# Bus_Isolator.net
KiCad netlist of a schematic drawn in EAGLE
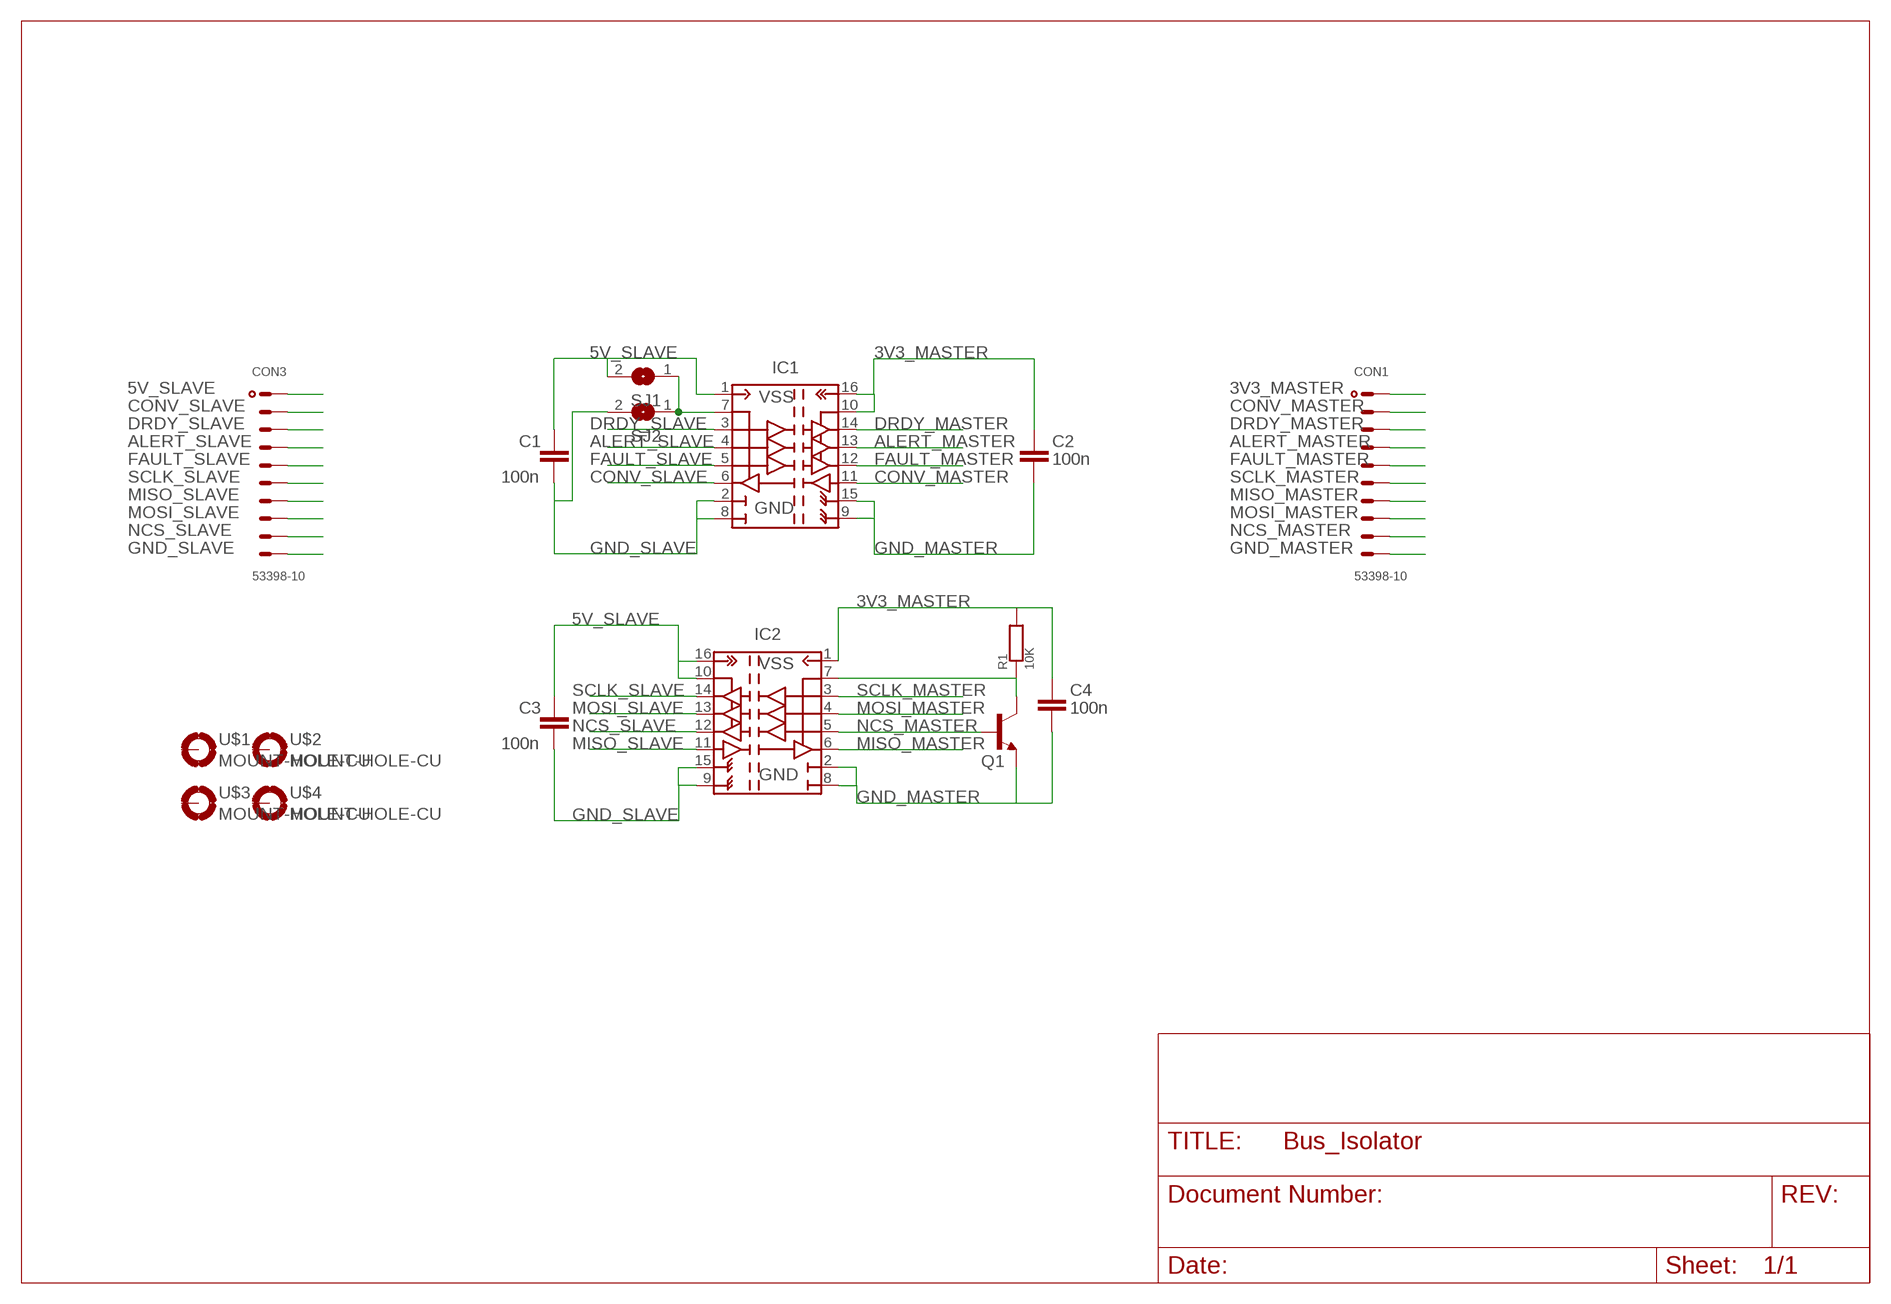
[diagram p0: schematic, sheet 1]

(export (version "E")
  (design (tool "Eeschema 10.0.6"))
  (components
    (comp (ref "C1")
      (value "100n")
      (footprint "eagle-import:C0805")
      (libsource (lib "eagle-import") (part "CSTD"))
    )
    (comp (ref "C2")
      (value "100n")
      (footprint "eagle-import:C0805")
      (libsource (lib "eagle-import") (part "CSTD"))
    )
    (comp (ref "C3")
      (value "100n")
      (footprint "eagle-import:C0805")
      (libsource (lib "eagle-import") (part "CSTD"))
    )
    (comp (ref "C4")
      (value "100n")
      (footprint "eagle-import:C0805")
      (libsource (lib "eagle-import") (part "CSTD"))
    )
    (comp (ref "CON1")
      (value "53398-10")
      (footprint "eagle-import:53398-10")
      (libsource (lib "eagle-import") (part "53?-10398"))
    )
    (comp (ref "CON3")
      (value "53398-10")
      (footprint "eagle-import:53398-10")
      (libsource (lib "eagle-import") (part "53?-10398"))
    )
    (comp (ref "IC1")
      (value "ISO7241")
      (footprint "eagle-import:R-PDSO-G16")
      (libsource (lib "eagle-import") (part "ISO7241"))
    )
    (comp (ref "IC2")
      (value "ISO7241")
      (footprint "eagle-import:R-PDSO-G16")
      (libsource (lib "eagle-import") (part "ISO7241"))
    )
    (comp (ref "Q1")
      (value "TRANSISTOR_NPNSOT23")
      (footprint "eagle-import:SOT23")
      (libsource (lib "eagle-import") (part "TRANSISTOR_NPNSOT23"))
    )
    (comp (ref "R1")
      (value "10K")
      (footprint "eagle-import:R0805")
      (libsource (lib "eagle-import") (part "R"))
    )
    (comp (ref "SJ1") (value "SJ") (footprint "eagle-import:SJ") (libsource (lib "eagle-import") (part "SJ")))
    (comp (ref "SJ2") (value "SJ") (footprint "eagle-import:SJ") (libsource (lib "eagle-import") (part "SJ")))
    (comp (ref "U$1")
      (value "MOUNT-HOLE-CU")
      (footprint "eagle-import:BOHRUNG-3,2-NUR-KUPFER")
      (libsource (lib "eagle-import") (part "MOUNT-HOLE-CU"))
    )
    (comp (ref "U$2")
      (value "MOUNT-HOLE-CU")
      (footprint "eagle-import:BOHRUNG-3,2-NUR-KUPFER")
      (libsource (lib "eagle-import") (part "MOUNT-HOLE-CU"))
    )
    (comp (ref "U$3")
      (value "MOUNT-HOLE-CU")
      (footprint "eagle-import:BOHRUNG-3,2-NUR-KUPFER")
      (libsource (lib "eagle-import") (part "MOUNT-HOLE-CU"))
    )
    (comp (ref "U$4")
      (value "MOUNT-HOLE-CU")
      (footprint "eagle-import:BOHRUNG-3,2-NUR-KUPFER")
      (libsource (lib "eagle-import") (part "MOUNT-HOLE-CU"))
    )
  )
  (nets
    (net (code "1") (name "/3V3_MASTER") (class "Default")
      (node (ref "C2") (pin "2") (pinfunction "2_2") (pintype "passive"))
      (node (ref "C4") (pin "2") (pinfunction "2_2") (pintype "passive"))
      (node (ref "CON1") (pin "1") (pinfunction "1_1") (pintype "passive"))
      (node (ref "IC1") (pin "10") (pinfunction "EN2_10") (pintype "bidirectional"))
      (node (ref "IC1") (pin "16") (pinfunction "VCC2_16") (pintype "bidirectional"))
      (node (ref "IC2") (pin "1") (pinfunction "VCC1_1") (pintype "bidirectional"))
      (node (ref "R1") (pin "2") (pinfunction "2_2") (pintype "passive"))
    )
    (net (code "2") (name "/5V_SLAVE") (class "Default")
      (node (ref "C1") (pin "2") (pinfunction "2_2") (pintype "passive"))
      (node (ref "C3") (pin "2") (pinfunction "2_2") (pintype "passive"))
      (node (ref "CON3") (pin "1") (pinfunction "1_1") (pintype "passive"))
      (node (ref "IC1") (pin "1") (pinfunction "VCC1_1") (pintype "bidirectional"))
      (node (ref "IC2") (pin "10") (pinfunction "EN2_10") (pintype "bidirectional"))
      (node (ref "IC2") (pin "16") (pinfunction "VCC2_16") (pintype "bidirectional"))
      (node (ref "SJ1") (pin "2") (pinfunction "2_2") (pintype "passive"))
    )
    (net (code "3") (name "/ALERT_MASTER") (class "Default")
      (node (ref "CON1") (pin "4") (pinfunction "4_4") (pintype "passive"))
      (node (ref "IC1") (pin "13") (pinfunction "OUT_B_13") (pintype "bidirectional"))
    )
    (net (code "4") (name "/ALERT_SLAVE") (class "Default")
      (node (ref "CON3") (pin "4") (pinfunction "4_4") (pintype "passive"))
      (node (ref "IC1") (pin "4") (pinfunction "IN_B_4") (pintype "bidirectional"))
    )
    (net (code "5") (name "/CONV_MASTER") (class "Default")
      (node (ref "CON1") (pin "2") (pinfunction "2_2") (pintype "passive"))
      (node (ref "IC1") (pin "11") (pinfunction "IN_D_11") (pintype "bidirectional"))
    )
    (net (code "6") (name "/CONV_SLAVE") (class "Default")
      (node (ref "CON3") (pin "2") (pinfunction "2_2") (pintype "passive"))
      (node (ref "IC1") (pin "6") (pinfunction "OUT_D_6") (pintype "bidirectional"))
    )
    (net (code "7") (name "/DRDY_MASTER") (class "Default")
      (node (ref "CON1") (pin "3") (pinfunction "3_3") (pintype "passive"))
      (node (ref "IC1") (pin "14") (pinfunction "OUT_A_14") (pintype "bidirectional"))
    )
    (net (code "8") (name "/DRDY_SLAVE") (class "Default")
      (node (ref "CON3") (pin "3") (pinfunction "3_3") (pintype "passive"))
      (node (ref "IC1") (pin "3") (pinfunction "IN_A_3") (pintype "bidirectional"))
    )
    (net (code "9") (name "/FAULT_MASTER") (class "Default")
      (node (ref "CON1") (pin "5") (pinfunction "5_5") (pintype "passive"))
      (node (ref "IC1") (pin "12") (pinfunction "OUT_C_12") (pintype "bidirectional"))
    )
    (net (code "10") (name "/FAULT_SLAVE") (class "Default")
      (node (ref "CON3") (pin "5") (pinfunction "5_5") (pintype "passive"))
      (node (ref "IC1") (pin "5") (pinfunction "IN_C_5") (pintype "bidirectional"))
    )
    (net (code "11") (name "/GND_MASTER") (class "Default")
      (node (ref "C2") (pin "1") (pinfunction "1_1") (pintype "passive"))
      (node (ref "C4") (pin "1") (pinfunction "1_1") (pintype "passive"))
      (node (ref "CON1") (pin "10") (pinfunction "10_10") (pintype "passive"))
      (node (ref "IC1") (pin "15") (pinfunction "GND21_15") (pintype "bidirectional"))
      (node (ref "IC1") (pin "9") (pinfunction "GND22_9") (pintype "bidirectional"))
      (node (ref "IC2") (pin "2") (pinfunction "GND11_2") (pintype "bidirectional"))
      (node (ref "IC2") (pin "8") (pinfunction "GND12_8") (pintype "bidirectional"))
      (node (ref "Q1") (pin "2") (pinfunction "E_2") (pintype "passive"))
    )
    (net (code "12") (name "/GND_SLAVE") (class "Default")
      (node (ref "C1") (pin "1") (pinfunction "1_1") (pintype "passive"))
      (node (ref "C3") (pin "1") (pinfunction "1_1") (pintype "passive"))
      (node (ref "CON3") (pin "10") (pinfunction "10_10") (pintype "passive"))
      (node (ref "IC1") (pin "2") (pinfunction "GND11_2") (pintype "bidirectional"))
      (node (ref "IC1") (pin "8") (pinfunction "GND12_8") (pintype "bidirectional"))
      (node (ref "IC2") (pin "15") (pinfunction "GND21_15") (pintype "bidirectional"))
      (node (ref "IC2") (pin "9") (pinfunction "GND22_9") (pintype "bidirectional"))
      (node (ref "SJ2") (pin "2") (pinfunction "2_2") (pintype "passive"))
    )
    (net (code "13") (name "/MISO_MASTER") (class "Default")
      (node (ref "CON1") (pin "7") (pinfunction "7_7") (pintype "passive"))
      (node (ref "IC2") (pin "6") (pinfunction "OUT_D_6") (pintype "bidirectional"))
    )
    (net (code "14") (name "/MISO_SLAVE") (class "Default")
      (node (ref "CON3") (pin "7") (pinfunction "7_7") (pintype "passive"))
      (node (ref "IC2") (pin "11") (pinfunction "IN_D_11") (pintype "bidirectional"))
    )
    (net (code "15") (name "/MOSI_MASTER") (class "Default")
      (node (ref "CON1") (pin "8") (pinfunction "8_8") (pintype "passive"))
      (node (ref "IC2") (pin "4") (pinfunction "IN_B_4") (pintype "bidirectional"))
    )
    (net (code "16") (name "/MOSI_SLAVE") (class "Default")
      (node (ref "CON3") (pin "8") (pinfunction "8_8") (pintype "passive"))
      (node (ref "IC2") (pin "13") (pinfunction "OUT_B_13") (pintype "bidirectional"))
    )
    (net (code "17") (name "/NCS_MASTER") (class "Default")
      (node (ref "CON1") (pin "9") (pinfunction "9_9") (pintype "passive"))
      (node (ref "IC2") (pin "5") (pinfunction "IN_C_5") (pintype "bidirectional"))
      (node (ref "Q1") (pin "1") (pinfunction "B_1") (pintype "passive"))
    )
    (net (code "18") (name "/NCS_SLAVE") (class "Default")
      (node (ref "CON3") (pin "9") (pinfunction "9_9") (pintype "passive"))
      (node (ref "IC2") (pin "12") (pinfunction "OUT_C_12") (pintype "bidirectional"))
    )
    (net (code "19") (name "/SCLK_MASTER") (class "Default")
      (node (ref "CON1") (pin "6") (pinfunction "6_6") (pintype "passive"))
      (node (ref "IC2") (pin "3") (pinfunction "IN_A_3") (pintype "bidirectional"))
    )
    (net (code "20") (name "/SCLK_SLAVE") (class "Default")
      (node (ref "CON3") (pin "6") (pinfunction "6_6") (pintype "passive"))
      (node (ref "IC2") (pin "14") (pinfunction "OUT_A_14") (pintype "bidirectional"))
    )
    (net (code "21") (name "Net-(IC1-EN1)") (class "Default")
      (node (ref "IC1") (pin "7") (pinfunction "EN1_7") (pintype "bidirectional"))
      (node (ref "SJ1") (pin "1") (pinfunction "1_1") (pintype "passive"))
      (node (ref "SJ2") (pin "1") (pinfunction "1_1") (pintype "passive"))
    )
    (net (code "22") (name "Net-(IC2-EN1)") (class "Default")
      (node (ref "IC2") (pin "7") (pinfunction "EN1_7") (pintype "bidirectional"))
      (node (ref "Q1") (pin "3") (pinfunction "C_3") (pintype "passive"))
      (node (ref "R1") (pin "1") (pinfunction "1_1") (pintype "passive"))
    )
    (net (code "23") (name "unconnected-(U$1-MOUNT-PadB3,2)") (class "Default")
      (node (ref "U$1") (pin "B3,2") (pinfunction "MOUNT_B3,2") (pintype "passive"))
    )
    (net (code "24") (name "unconnected-(U$2-MOUNT-PadB3,2)") (class "Default")
      (node (ref "U$2") (pin "B3,2") (pinfunction "MOUNT_B3,2") (pintype "passive"))
    )
    (net (code "25") (name "unconnected-(U$3-MOUNT-PadB3,2)") (class "Default")
      (node (ref "U$3") (pin "B3,2") (pinfunction "MOUNT_B3,2") (pintype "passive"))
    )
    (net (code "26") (name "unconnected-(U$4-MOUNT-PadB3,2)") (class "Default")
      (node (ref "U$4") (pin "B3,2") (pinfunction "MOUNT_B3,2") (pintype "passive"))
    )
  )
)
